# gal-psg.net
KiCad netlist of a schematic drawn in EAGLE
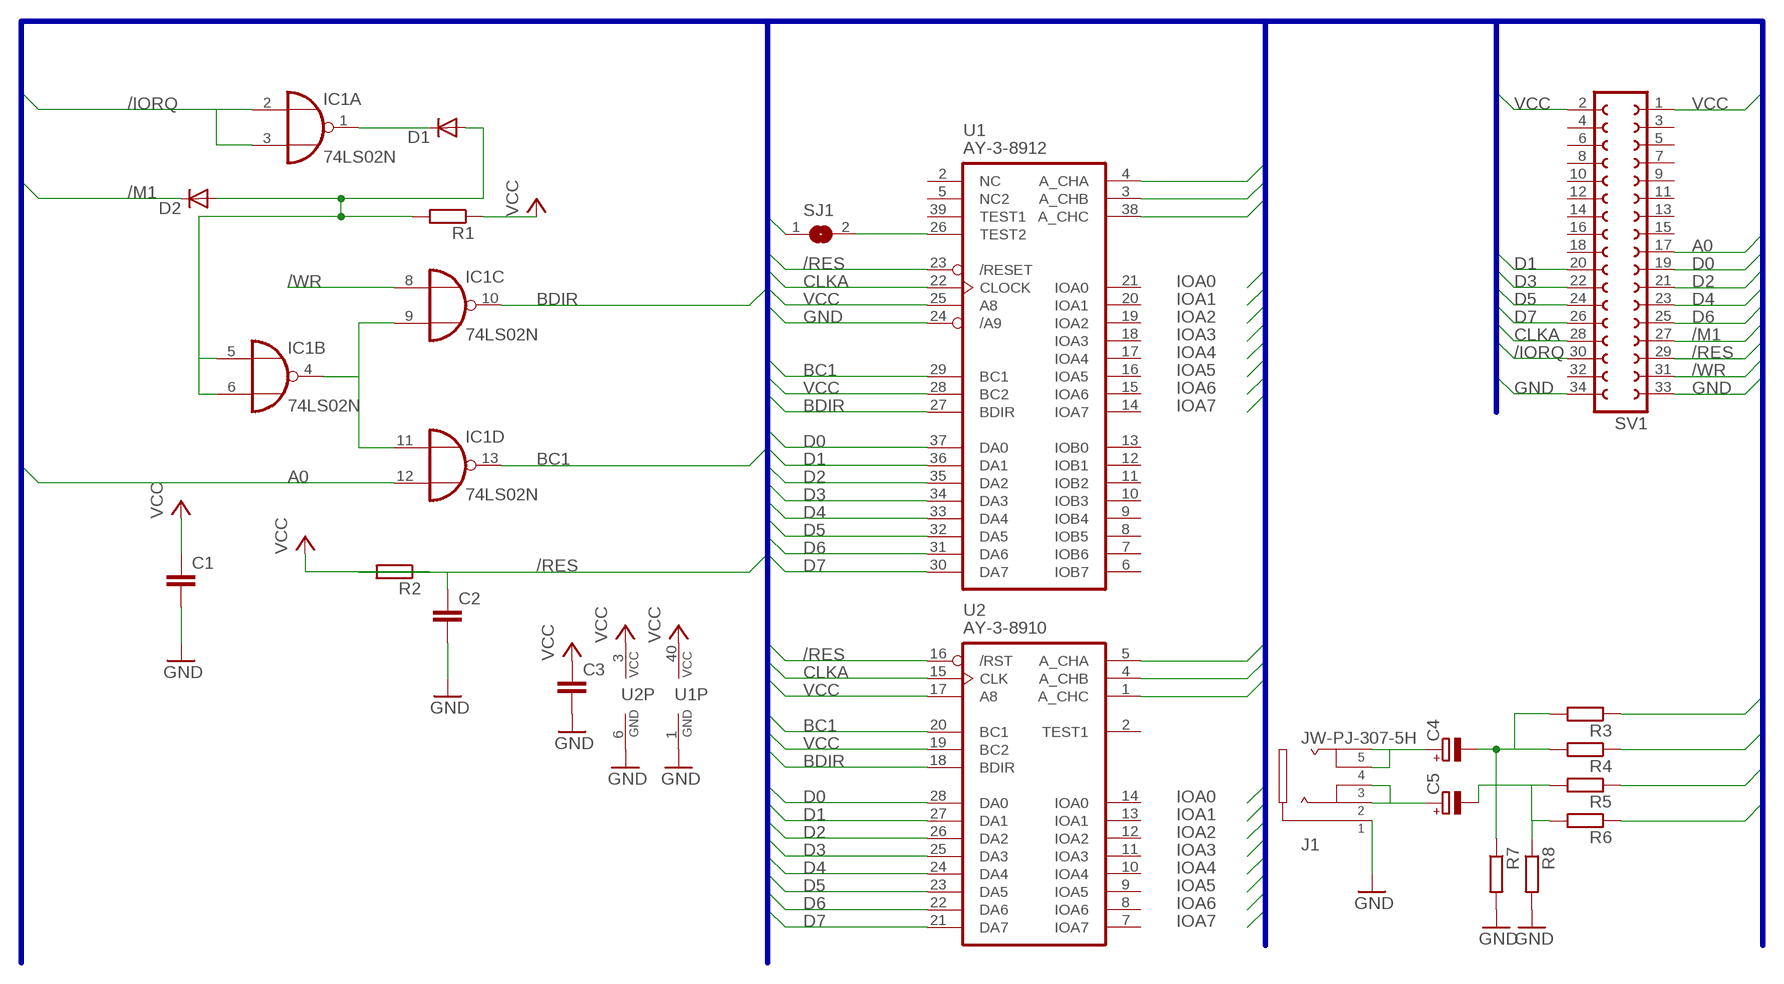
[diagram p0: schematic, sheet 1]

(export (version "E")
  (design (tool "Eeschema 10.0.6"))
  (components
    (comp (ref "C1")
      (value "C-EU025-024X044")
      (footprint "eagle-import:C025-024X044")
      (libsource (lib "eagle-import") (part "C-EU025-024X044"))
    )
    (comp (ref "C2")
      (value "C-EU025-024X044")
      (footprint "eagle-import:C025-024X044")
      (libsource (lib "eagle-import") (part "C-EU025-024X044"))
    )
    (comp (ref "C3")
      (value "C-EU025-024X044")
      (footprint "eagle-import:C025-024X044")
      (libsource (lib "eagle-import") (part "C-EU025-024X044"))
    )
    (comp (ref "C4")
      (value "CPOL-EUE1.8-4")
      (footprint "eagle-import:E1,8-4")
      (libsource (lib "eagle-import") (part "CPOL-EUE1.8-4"))
    )
    (comp (ref "C5")
      (value "CPOL-EUE1.8-4")
      (footprint "eagle-import:E1,8-4")
      (libsource (lib "eagle-import") (part "CPOL-EUE1.8-4"))
    )
    (comp (ref "D1")
      (value "DIODE-D-2.5")
      (footprint "eagle-import:D-2.5")
      (libsource (lib "eagle-import") (part "DIODE-D-2.5"))
    )
    (comp (ref "D2")
      (value "DIODE-D-2.5")
      (footprint "eagle-import:D-2.5")
      (libsource (lib "eagle-import") (part "DIODE-D-2.5"))
    )
    (comp (ref "IC1")
      (value "74LS02N")
      (footprint "eagle-import:DIL14")
      (libsource (lib "eagle-import") (part "7402NLS"))
    )
    (comp (ref "J1")
      (value "JW-PJ-307-5H")
      (footprint "eagle-import:JW-PJ-307-5H")
      (libsource (lib "eagle-import") (part "JW-PJ-307-5H"))
    )
    (comp (ref "R1")
      (value "R-EU_0207/2V")
      (footprint "eagle-import:0207_2V")
      (libsource (lib "eagle-import") (part "R-EU_0207/2V"))
    )
    (comp (ref "R2")
      (value "R-EU_0207/2V")
      (footprint "eagle-import:0207_2V")
      (libsource (lib "eagle-import") (part "R-EU_0207/2V"))
    )
    (comp (ref "R3")
      (value "R-EU_0207/2V")
      (footprint "eagle-import:0207_2V")
      (libsource (lib "eagle-import") (part "R-EU_0207/2V"))
    )
    (comp (ref "R4")
      (value "R-EU_0207/2V")
      (footprint "eagle-import:0207_2V")
      (libsource (lib "eagle-import") (part "R-EU_0207/2V"))
    )
    (comp (ref "R5")
      (value "R-EU_0207/2V")
      (footprint "eagle-import:0207_2V")
      (libsource (lib "eagle-import") (part "R-EU_0207/2V"))
    )
    (comp (ref "R6")
      (value "R-EU_0207/2V")
      (footprint "eagle-import:0207_2V")
      (libsource (lib "eagle-import") (part "R-EU_0207/2V"))
    )
    (comp (ref "R7")
      (value "R-EU_0207/2V")
      (footprint "eagle-import:0207_2V")
      (libsource (lib "eagle-import") (part "R-EU_0207/2V"))
    )
    (comp (ref "R8")
      (value "R-EU_0207/2V")
      (footprint "eagle-import:0207_2V")
      (libsource (lib "eagle-import") (part "R-EU_0207/2V"))
    )
    (comp (ref "SJ1") (value "SJ") (footprint "eagle-import:SJ") (libsource (lib "eagle-import") (part "SJ")))
    (comp (ref "SV1")
      (value "FE17-2W")
      (footprint "eagle-import:FE17-2W")
      (libsource (lib "eagle-import") (part "FE17-2W"))
    )
    (comp (ref "U1")
      (value "AY-3-8912")
      (footprint "eagle-import:DIL40")
      (libsource (lib "eagle-import") (part "AY-3-8912"))
    )
    (comp (ref "U2")
      (value "AY-3-8910")
      (footprint "eagle-import:DIL28-6")
      (libsource (lib "eagle-import") (part "AY-3-8910"))
    )
  )
  (nets
    (net (code "1") (name "/A") (class "Default")
      (node (ref "R3") (pin "1") (pinfunction "1_1") (pintype "passive"))
      (node (ref "U1") (pin "4") (pinfunction "A_CHA_4") (pintype "output"))
      (node (ref "U2") (pin "5") (pinfunction "A_CHA_5") (pintype "output"))
    )
    (net (code "2") (name "/A0") (class "Default")
      (node (ref "IC1") (pin "12") (pinfunction "I1_12") (pintype "input"))
      (node (ref "SV1") (pin "17") (pinfunction "17_17") (pintype "passive"))
    )
    (net (code "3") (name "/B") (class "Default")
      (node (ref "R4") (pin "1") (pinfunction "1_1") (pintype "passive"))
      (node (ref "R5") (pin "1") (pinfunction "1_1") (pintype "passive"))
      (node (ref "U1") (pin "3") (pinfunction "A_CHB_3") (pintype "output"))
      (node (ref "U2") (pin "4") (pinfunction "A_CHB_4") (pintype "output"))
    )
    (net (code "4") (name "/BC1") (class "Default")
      (node (ref "IC1") (pin "13") (pinfunction "O_13") (pintype "output"))
      (node (ref "U1") (pin "29") (pinfunction "BC1_29") (pintype "input"))
      (node (ref "U2") (pin "20") (pinfunction "BC1_20") (pintype "input"))
    )
    (net (code "5") (name "/BDIR") (class "Default")
      (node (ref "IC1") (pin "10") (pinfunction "O_10") (pintype "output"))
      (node (ref "U1") (pin "27") (pinfunction "BDIR_27") (pintype "input"))
      (node (ref "U2") (pin "18") (pinfunction "BDIR_18") (pintype "input"))
    )
    (net (code "6") (name "/C") (class "Default")
      (node (ref "R6") (pin "1") (pinfunction "1_1") (pintype "passive"))
      (node (ref "U1") (pin "38") (pinfunction "A_CHC_38") (pintype "output"))
      (node (ref "U2") (pin "1") (pinfunction "A_CHC_1") (pintype "output"))
    )
    (net (code "7") (name "/CLKA") (class "Default")
      (node (ref "SV1") (pin "28") (pinfunction "28_28") (pintype "passive"))
      (node (ref "U1") (pin "22") (pinfunction "CLOCK_22") (pintype "input"))
      (node (ref "U2") (pin "15") (pinfunction "CLK_15") (pintype "input"))
    )
    (net (code "8") (name "/D0") (class "Default")
      (node (ref "SV1") (pin "19") (pinfunction "19_19") (pintype "passive"))
      (node (ref "U1") (pin "37") (pinfunction "DA0_37") (pintype "bidirectional"))
      (node (ref "U2") (pin "28") (pinfunction "DA0_28") (pintype "bidirectional"))
    )
    (net (code "9") (name "/D1") (class "Default")
      (node (ref "SV1") (pin "20") (pinfunction "20_20") (pintype "passive"))
      (node (ref "U1") (pin "36") (pinfunction "DA1_36") (pintype "bidirectional"))
      (node (ref "U2") (pin "27") (pinfunction "DA1_27") (pintype "bidirectional"))
    )
    (net (code "10") (name "/D2") (class "Default")
      (node (ref "SV1") (pin "21") (pinfunction "21_21") (pintype "passive"))
      (node (ref "U1") (pin "35") (pinfunction "DA2_35") (pintype "bidirectional"))
      (node (ref "U2") (pin "26") (pinfunction "DA2_26") (pintype "bidirectional"))
    )
    (net (code "11") (name "/D3") (class "Default")
      (node (ref "SV1") (pin "22") (pinfunction "22_22") (pintype "passive"))
      (node (ref "U1") (pin "34") (pinfunction "DA3_34") (pintype "bidirectional"))
      (node (ref "U2") (pin "25") (pinfunction "DA3_25") (pintype "bidirectional"))
    )
    (net (code "12") (name "/D4") (class "Default")
      (node (ref "SV1") (pin "23") (pinfunction "23_23") (pintype "passive"))
      (node (ref "U1") (pin "33") (pinfunction "DA4_33") (pintype "bidirectional"))
      (node (ref "U2") (pin "24") (pinfunction "DA4_24") (pintype "bidirectional"))
    )
    (net (code "13") (name "/D5") (class "Default")
      (node (ref "SV1") (pin "24") (pinfunction "24_24") (pintype "passive"))
      (node (ref "U1") (pin "32") (pinfunction "DA5_32") (pintype "bidirectional"))
      (node (ref "U2") (pin "23") (pinfunction "DA5_23") (pintype "bidirectional"))
    )
    (net (code "14") (name "/D6") (class "Default")
      (node (ref "SV1") (pin "25") (pinfunction "25_25") (pintype "passive"))
      (node (ref "U1") (pin "31") (pinfunction "DA6_31") (pintype "bidirectional"))
      (node (ref "U2") (pin "22") (pinfunction "DA6_22") (pintype "bidirectional"))
    )
    (net (code "15") (name "/D7") (class "Default")
      (node (ref "SV1") (pin "26") (pinfunction "26_26") (pintype "passive"))
      (node (ref "U1") (pin "30") (pinfunction "DA7_30") (pintype "bidirectional"))
      (node (ref "U2") (pin "21") (pinfunction "DA7_21") (pintype "bidirectional"))
    )
    (net (code "24") (name "/{slash}IORQ") (class "Default")
      (node (ref "IC1") (pin "2") (pinfunction "I0_2") (pintype "input"))
      (node (ref "IC1") (pin "3") (pinfunction "I1_3") (pintype "input"))
      (node (ref "SV1") (pin "30") (pinfunction "30_30") (pintype "passive"))
    )
    (net (code "25") (name "/{slash}M1") (class "Default")
      (node (ref "D2") (pin "C") (pinfunction "C_C") (pintype "passive"))
      (node (ref "SV1") (pin "27") (pinfunction "27_27") (pintype "passive"))
    )
    (net (code "26") (name "/{slash}RES") (class "Default")
      (node (ref "C2") (pin "1") (pinfunction "1_1") (pintype "passive"))
      (node (ref "R2") (pin "2") (pinfunction "2_2") (pintype "passive"))
      (node (ref "SV1") (pin "29") (pinfunction "29_29") (pintype "passive"))
      (node (ref "U1") (pin "23") (pinfunction "/RESET_23") (pintype "input"))
      (node (ref "U2") (pin "16") (pinfunction "/RST_16") (pintype "input"))
    )
    (net (code "27") (name "/{slash}WR") (class "Default")
      (node (ref "IC1") (pin "8") (pinfunction "I0_8") (pintype "input"))
      (node (ref "SV1") (pin "31") (pinfunction "31_31") (pintype "passive"))
    )
    (net (code "28") (name "GND") (class "Default")
      (node (ref "C1") (pin "2") (pinfunction "2_2") (pintype "passive"))
      (node (ref "C2") (pin "2") (pinfunction "2_2") (pintype "passive"))
      (node (ref "C3") (pin "2") (pinfunction "2_2") (pintype "passive"))
      (node (ref "J1") (pin "1") (pinfunction "1_1") (pintype "passive"))
      (node (ref "R7") (pin "2") (pinfunction "2_2") (pintype "passive"))
      (node (ref "R8") (pin "2") (pinfunction "2_2") (pintype "passive"))
      (node (ref "SJ1") (pin "1") (pinfunction "1_1") (pintype "passive"))
      (node (ref "SV1") (pin "33") (pinfunction "33_33") (pintype "passive"))
      (node (ref "SV1") (pin "34") (pinfunction "34_34") (pintype "passive"))
      (node (ref "U1") (pin "1") (pinfunction "GND_1") (pintype "power_in"))
      (node (ref "U1") (pin "24") (pinfunction "/A9_24") (pintype "input"))
      (node (ref "U2") (pin "6") (pinfunction "GND_6") (pintype "power_in"))
    )
    (net (code "29") (name "Net-(C4-Pad+)") (class "Default")
      (node (ref "C4") (pin "+") (pinfunction "+_+") (pintype "passive"))
      (node (ref "J1") (pin "4") (pinfunction "4_4") (pintype "passive"))
      (node (ref "J1") (pin "5") (pinfunction "5_5") (pintype "passive"))
    )
    (net (code "30") (name "Net-(C4-Pad-)") (class "Default")
      (node (ref "C4") (pin "-") (pinfunction "-_-") (pintype "passive"))
      (node (ref "R3") (pin "2") (pinfunction "2_2") (pintype "passive"))
      (node (ref "R4") (pin "2") (pinfunction "2_2") (pintype "passive"))
      (node (ref "R7") (pin "1") (pinfunction "1_1") (pintype "passive"))
    )
    (net (code "31") (name "Net-(C5-Pad+)") (class "Default")
      (node (ref "C5") (pin "+") (pinfunction "+_+") (pintype "passive"))
      (node (ref "J1") (pin "2") (pinfunction "2_2") (pintype "passive"))
      (node (ref "J1") (pin "3") (pinfunction "3_3") (pintype "passive"))
    )
    (net (code "32") (name "Net-(C5-Pad-)") (class "Default")
      (node (ref "C5") (pin "-") (pinfunction "-_-") (pintype "passive"))
      (node (ref "R5") (pin "2") (pinfunction "2_2") (pintype "passive"))
      (node (ref "R6") (pin "2") (pinfunction "2_2") (pintype "passive"))
      (node (ref "R8") (pin "1") (pinfunction "1_1") (pintype "passive"))
    )
    (net (code "33") (name "Net-(IC1A-O)") (class "Default")
      (node (ref "D1") (pin "C") (pinfunction "C_C") (pintype "passive"))
      (node (ref "IC1") (pin "1") (pinfunction "O_1") (pintype "output"))
    )
    (net (code "34") (name "Net-(IC1B-I0)") (class "Default")
      (node (ref "D1") (pin "A") (pinfunction "A_A") (pintype "passive"))
      (node (ref "D2") (pin "A") (pinfunction "A_A") (pintype "passive"))
      (node (ref "IC1") (pin "5") (pinfunction "I0_5") (pintype "input"))
      (node (ref "IC1") (pin "6") (pinfunction "I1_6") (pintype "input"))
      (node (ref "R1") (pin "2") (pinfunction "2_2") (pintype "passive"))
    )
    (net (code "35") (name "Net-(IC1B-O)") (class "Default")
      (node (ref "IC1") (pin "11") (pinfunction "I0_11") (pintype "input"))
      (node (ref "IC1") (pin "4") (pinfunction "O_4") (pintype "output"))
      (node (ref "IC1") (pin "9") (pinfunction "I1_9") (pintype "input"))
    )
    (net (code "36") (name "Net-(U1A-TEST2)") (class "Default")
      (node (ref "SJ1") (pin "2") (pinfunction "2_2") (pintype "passive"))
      (node (ref "U1") (pin "26") (pinfunction "TEST2_26") (pintype "input"))
    )
    (net (code "37") (name "VCC") (class "Default")
      (node (ref "C1") (pin "1") (pinfunction "1_1") (pintype "passive"))
      (node (ref "C3") (pin "1") (pinfunction "1_1") (pintype "passive"))
      (node (ref "R1") (pin "1") (pinfunction "1_1") (pintype "passive"))
      (node (ref "R2") (pin "1") (pinfunction "1_1") (pintype "passive"))
      (node (ref "SV1") (pin "1") (pinfunction "1_1") (pintype "passive"))
      (node (ref "SV1") (pin "2") (pinfunction "2_2") (pintype "passive"))
      (node (ref "U1") (pin "25") (pinfunction "A8_25") (pintype "input"))
      (node (ref "U1") (pin "28") (pinfunction "BC2_28") (pintype "input"))
      (node (ref "U1") (pin "40") (pinfunction "VCC_40") (pintype "power_in"))
      (node (ref "U2") (pin "17") (pinfunction "A8_17") (pintype "input"))
      (node (ref "U2") (pin "19") (pinfunction "BC2_19") (pintype "input"))
      (node (ref "U2") (pin "3") (pinfunction "VCC_3") (pintype "power_in"))
    )
    (net (code "38") (name "unconnected-(SV1-Pad3)") (class "Default")
      (node (ref "SV1") (pin "3") (pinfunction "3_3") (pintype "passive"))
    )
    (net (code "39") (name "unconnected-(SV1-Pad4)") (class "Default")
      (node (ref "SV1") (pin "4") (pinfunction "4_4") (pintype "passive"))
    )
    (net (code "40") (name "unconnected-(SV1-Pad5)") (class "Default")
      (node (ref "SV1") (pin "5") (pinfunction "5_5") (pintype "passive"))
    )
    (net (code "41") (name "unconnected-(SV1-Pad6)") (class "Default")
      (node (ref "SV1") (pin "6") (pinfunction "6_6") (pintype "passive"))
    )
    (net (code "42") (name "unconnected-(SV1-Pad7)") (class "Default")
      (node (ref "SV1") (pin "7") (pinfunction "7_7") (pintype "passive"))
    )
    (net (code "43") (name "unconnected-(SV1-Pad8)") (class "Default")
      (node (ref "SV1") (pin "8") (pinfunction "8_8") (pintype "passive"))
    )
    (net (code "44") (name "unconnected-(SV1-Pad9)") (class "Default")
      (node (ref "SV1") (pin "9") (pinfunction "9_9") (pintype "passive"))
    )
    (net (code "45") (name "unconnected-(SV1-Pad10)") (class "Default")
      (node (ref "SV1") (pin "10") (pinfunction "10_10") (pintype "passive"))
    )
    (net (code "46") (name "unconnected-(SV1-Pad11)") (class "Default")
      (node (ref "SV1") (pin "11") (pinfunction "11_11") (pintype "passive"))
    )
    (net (code "47") (name "unconnected-(SV1-Pad12)") (class "Default")
      (node (ref "SV1") (pin "12") (pinfunction "12_12") (pintype "passive"))
    )
    (net (code "48") (name "unconnected-(SV1-Pad13)") (class "Default")
      (node (ref "SV1") (pin "13") (pinfunction "13_13") (pintype "passive"))
    )
    (net (code "49") (name "unconnected-(SV1-Pad14)") (class "Default")
      (node (ref "SV1") (pin "14") (pinfunction "14_14") (pintype "passive"))
    )
    (net (code "50") (name "unconnected-(SV1-Pad15)") (class "Default")
      (node (ref "SV1") (pin "15") (pinfunction "15_15") (pintype "passive"))
    )
    (net (code "51") (name "unconnected-(SV1-Pad16)") (class "Default")
      (node (ref "SV1") (pin "16") (pinfunction "16_16") (pintype "passive"))
    )
    (net (code "52") (name "unconnected-(SV1-Pad18)") (class "Default")
      (node (ref "SV1") (pin "18") (pinfunction "18_18") (pintype "passive"))
    )
    (net (code "53") (name "unconnected-(SV1-Pad32)") (class "Default")
      (node (ref "SV1") (pin "32") (pinfunction "32_32") (pintype "passive"))
    )
    (net (code "54") (name "unconnected-(U1A-IOA0-Pad21)") (class "Default")
      (node (ref "U1") (pin "21") (pinfunction "IOA0_21") (pintype "bidirectional"))
    )
    (net (code "55") (name "unconnected-(U1A-IOA1-Pad20)") (class "Default")
      (node (ref "U1") (pin "20") (pinfunction "IOA1_20") (pintype "bidirectional"))
    )
    (net (code "56") (name "unconnected-(U1A-IOA2-Pad19)") (class "Default")
      (node (ref "U1") (pin "19") (pinfunction "IOA2_19") (pintype "bidirectional"))
    )
    (net (code "57") (name "unconnected-(U1A-IOA3-Pad18)") (class "Default")
      (node (ref "U1") (pin "18") (pinfunction "IOA3_18") (pintype "bidirectional"))
    )
    (net (code "58") (name "unconnected-(U1A-IOA4-Pad17)") (class "Default")
      (node (ref "U1") (pin "17") (pinfunction "IOA4_17") (pintype "bidirectional"))
    )
    (net (code "59") (name "unconnected-(U1A-IOA5-Pad16)") (class "Default")
      (node (ref "U1") (pin "16") (pinfunction "IOA5_16") (pintype "bidirectional"))
    )
    (net (code "60") (name "unconnected-(U1A-IOA6-Pad15)") (class "Default")
      (node (ref "U1") (pin "15") (pinfunction "IOA6_15") (pintype "bidirectional"))
    )
    (net (code "61") (name "unconnected-(U1A-IOA7-Pad14)") (class "Default")
      (node (ref "U1") (pin "14") (pinfunction "IOA7_14") (pintype "bidirectional"))
    )
    (net (code "62") (name "unconnected-(U1A-IOB0-Pad13)") (class "Default")
      (node (ref "U1") (pin "13") (pinfunction "IOB0_13") (pintype "bidirectional"))
    )
    (net (code "63") (name "unconnected-(U1A-IOB1-Pad12)") (class "Default")
      (node (ref "U1") (pin "12") (pinfunction "IOB1_12") (pintype "bidirectional"))
    )
    (net (code "64") (name "unconnected-(U1A-IOB2-Pad11)") (class "Default")
      (node (ref "U1") (pin "11") (pinfunction "IOB2_11") (pintype "bidirectional"))
    )
    (net (code "65") (name "unconnected-(U1A-IOB3-Pad10)") (class "Default")
      (node (ref "U1") (pin "10") (pinfunction "IOB3_10") (pintype "bidirectional"))
    )
    (net (code "66") (name "unconnected-(U1A-IOB4-Pad9)") (class "Default")
      (node (ref "U1") (pin "9") (pinfunction "IOB4_9") (pintype "bidirectional"))
    )
    (net (code "67") (name "unconnected-(U1A-IOB5-Pad8)") (class "Default")
      (node (ref "U1") (pin "8") (pinfunction "IOB5_8") (pintype "bidirectional"))
    )
    (net (code "68") (name "unconnected-(U1A-IOB6-Pad7)") (class "Default")
      (node (ref "U1") (pin "7") (pinfunction "IOB6_7") (pintype "bidirectional"))
    )
    (net (code "69") (name "unconnected-(U1A-IOB7-Pad6)") (class "Default")
      (node (ref "U1") (pin "6") (pinfunction "IOB7_6") (pintype "bidirectional"))
    )
    (net (code "70") (name "unconnected-(U1A-NC-Pad2)") (class "Default")
      (node (ref "U1") (pin "2") (pinfunction "NC_2") (pintype "no_connect"))
    )
    (net (code "71") (name "unconnected-(U1A-NC2-Pad5)") (class "Default")
      (node (ref "U1") (pin "5") (pinfunction "NC2_5") (pintype "no_connect"))
    )
    (net (code "72") (name "unconnected-(U1A-TEST1-Pad39)") (class "Default")
      (node (ref "U1") (pin "39") (pinfunction "TEST1_39") (pintype "input"))
    )
    (net (code "73") (name "unconnected-(U2A-IOA0-Pad14)") (class "Default")
      (node (ref "U2") (pin "14") (pinfunction "IOA0_14") (pintype "bidirectional"))
    )
    (net (code "74") (name "unconnected-(U2A-IOA1-Pad13)") (class "Default")
      (node (ref "U2") (pin "13") (pinfunction "IOA1_13") (pintype "bidirectional"))
    )
    (net (code "75") (name "unconnected-(U2A-IOA2-Pad12)") (class "Default")
      (node (ref "U2") (pin "12") (pinfunction "IOA2_12") (pintype "bidirectional"))
    )
    (net (code "76") (name "unconnected-(U2A-IOA3-Pad11)") (class "Default")
      (node (ref "U2") (pin "11") (pinfunction "IOA3_11") (pintype "bidirectional"))
    )
    (net (code "77") (name "unconnected-(U2A-IOA4-Pad10)") (class "Default")
      (node (ref "U2") (pin "10") (pinfunction "IOA4_10") (pintype "bidirectional"))
    )
    (net (code "78") (name "unconnected-(U2A-IOA5-Pad9)") (class "Default")
      (node (ref "U2") (pin "9") (pinfunction "IOA5_9") (pintype "bidirectional"))
    )
    (net (code "79") (name "unconnected-(U2A-IOA6-Pad8)") (class "Default")
      (node (ref "U2") (pin "8") (pinfunction "IOA6_8") (pintype "bidirectional"))
    )
    (net (code "80") (name "unconnected-(U2A-IOA7-Pad7)") (class "Default")
      (node (ref "U2") (pin "7") (pinfunction "IOA7_7") (pintype "bidirectional"))
    )
    (net (code "81") (name "unconnected-(U2A-TEST1-Pad2)") (class "Default")
      (node (ref "U2") (pin "2") (pinfunction "TEST1_2") (pintype "input"))
    )
  )
)
